# schem.net
KiCad netlist of a schematic drawn in EAGLE
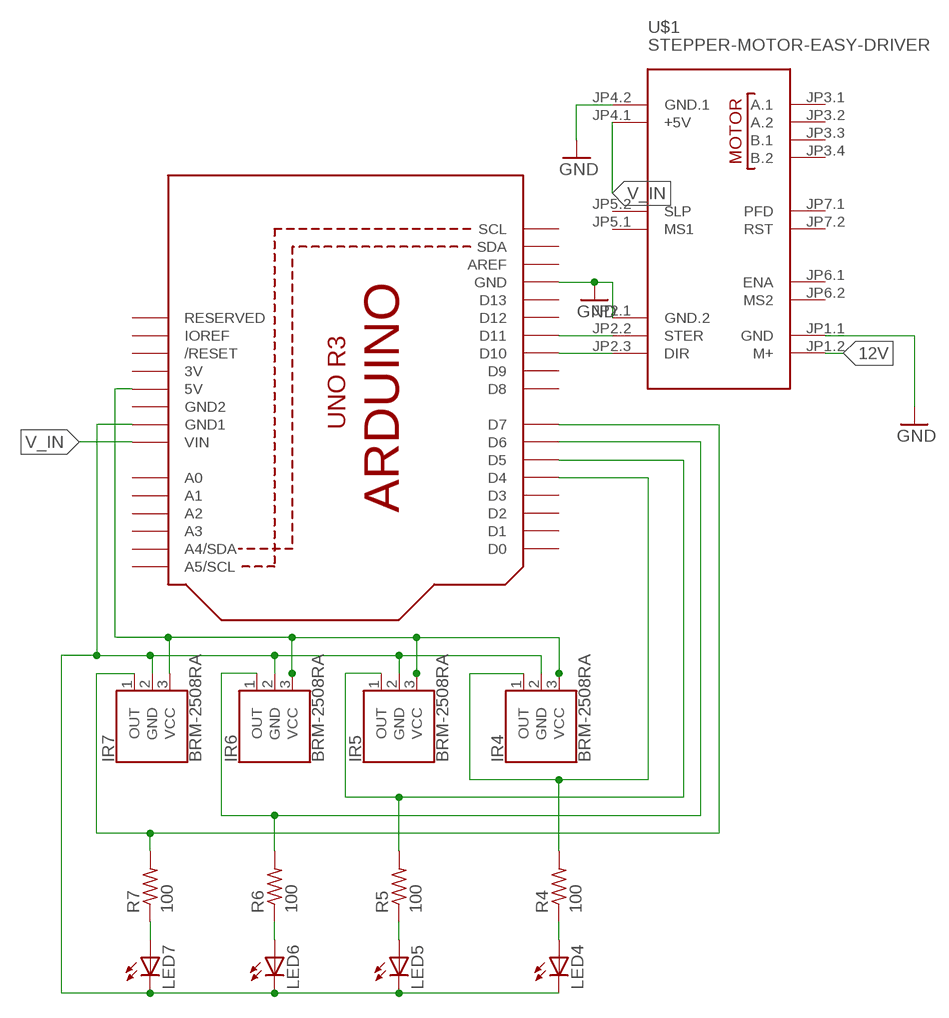
[diagram p0: schematic, sheet 1]

(export (version "E")
  (design (tool "Eeschema 10.0.6"))
  (components
    (comp (ref "IR4")
      (value "BRM-2508RA")
      (footprint "eagle-import:BRM-2508")
      (libsource (lib "eagle-import") (part "BRM-2508RA"))
    )
    (comp (ref "IR5")
      (value "BRM-2508RA")
      (footprint "eagle-import:BRM-2508")
      (libsource (lib "eagle-import") (part "BRM-2508RA"))
    )
    (comp (ref "IR6")
      (value "BRM-2508RA")
      (footprint "eagle-import:BRM-2508")
      (libsource (lib "eagle-import") (part "BRM-2508RA"))
    )
    (comp (ref "IR7")
      (value "BRM-2508RA")
      (footprint "eagle-import:BRM-2508")
      (libsource (lib "eagle-import") (part "BRM-2508RA"))
    )
    (comp (ref "LED4")
      (value "LED5MM")
      (footprint "eagle-import:LED5MM")
      (libsource (lib "eagle-import") (part "LED5MM"))
    )
    (comp (ref "LED5")
      (value "LED5MM")
      (footprint "eagle-import:LED5MM")
      (libsource (lib "eagle-import") (part "LED5MM"))
    )
    (comp (ref "LED6")
      (value "LED5MM")
      (footprint "eagle-import:LED5MM")
      (libsource (lib "eagle-import") (part "LED5MM"))
    )
    (comp (ref "LED7")
      (value "LED5MM")
      (footprint "eagle-import:LED5MM")
      (libsource (lib "eagle-import") (part "LED5MM"))
    )
    (comp (ref "R4")
      (value "100")
      (footprint "eagle-import:0805-THM")
      (libsource (lib "eagle-import") (part "FLIPFLOP-RES"))
    )
    (comp (ref "R5")
      (value "100")
      (footprint "eagle-import:0805-THM")
      (libsource (lib "eagle-import") (part "FLIPFLOP-RES"))
    )
    (comp (ref "R6")
      (value "100")
      (footprint "eagle-import:0805-THM")
      (libsource (lib "eagle-import") (part "FLIPFLOP-RES"))
    )
    (comp (ref "R7")
      (value "100")
      (footprint "eagle-import:0805-THM")
      (libsource (lib "eagle-import") (part "FLIPFLOP-RES"))
    )
    (comp (ref "U$1")
      (value "STEPPER-MOTOR-EASY-DRIVER")
      (footprint "eagle-import:STEPPER-MOTOR-EASY-DRIVER")
      (libsource (lib "eagle-import") (part "STEPPER-MOTOR-EASY-DRIVER"))
    )
    (comp (ref "U1")
      (value "ARDUINOR3-BPLACE")
      (footprint "eagle-import:ARDUINOR3-BPLACE")
      (libsource (lib "eagle-import") (part "ARDUINOR3-BPLACE"))
    )
  )
  (nets
    (net (code "1") (name "/3V") (class "Default")
      (node (ref "U1") (pin "3V") (pinfunction "3V_3V") (pintype "power_in"))
    )
    (net (code "2") (name "/GND2") (class "Default")
      (node (ref "U1") (pin "GND2") (pinfunction "GND2_GND2") (pintype "power_in"))
    )
    (net (code "3") (name "12V") (class "Default")
      (node (ref "U$1") (pin "JP1.2") (pinfunction "M+_JP1.2") (pintype "bidirectional"))
    )
    (net (code "4") (name "GND") (class "Default")
      (node (ref "U$1") (pin "JP1.1") (pinfunction "GND_JP1.1") (pintype "bidirectional"))
      (node (ref "U$1") (pin "JP2.1") (pinfunction "GND.2_JP2.1") (pintype "bidirectional"))
      (node (ref "U$1") (pin "JP4.2") (pinfunction "GND.1_JP4.2") (pintype "bidirectional"))
      (node (ref "U1") (pin "GND") (pinfunction "GND_GND") (pintype "power_in"))
    )
    (net (code "5") (name "Net-(IR4-GND)") (class "Default")
      (node (ref "IR4") (pin "2") (pinfunction "GND_2") (pintype "bidirectional"))
      (node (ref "IR5") (pin "2") (pinfunction "GND_2") (pintype "bidirectional"))
      (node (ref "IR6") (pin "2") (pinfunction "GND_2") (pintype "bidirectional"))
      (node (ref "IR7") (pin "2") (pinfunction "GND_2") (pintype "bidirectional"))
      (node (ref "LED4") (pin "K") (pinfunction "C_K") (pintype "passive"))
      (node (ref "LED5") (pin "K") (pinfunction "C_K") (pintype "passive"))
      (node (ref "LED6") (pin "K") (pinfunction "C_K") (pintype "passive"))
      (node (ref "LED7") (pin "K") (pinfunction "C_K") (pintype "passive"))
      (node (ref "U1") (pin "GND1") (pinfunction "GND1_GND1") (pintype "power_in"))
    )
    (net (code "6") (name "Net-(IR4-OUT)") (class "Default")
      (node (ref "IR4") (pin "1") (pinfunction "OUT_1") (pintype "bidirectional"))
      (node (ref "R4") (pin "2") (pinfunction "2_2") (pintype "passive"))
      (node (ref "U1") (pin "D4") (pinfunction "D4_D4") (pintype "bidirectional"))
    )
    (net (code "7") (name "Net-(IR4-VCC)") (class "Default")
      (node (ref "IR4") (pin "3") (pinfunction "VCC_3") (pintype "bidirectional"))
      (node (ref "IR5") (pin "3") (pinfunction "VCC_3") (pintype "bidirectional"))
      (node (ref "IR6") (pin "3") (pinfunction "VCC_3") (pintype "bidirectional"))
      (node (ref "IR7") (pin "3") (pinfunction "VCC_3") (pintype "bidirectional"))
      (node (ref "U1") (pin "5V") (pinfunction "5V_5V") (pintype "power_in"))
    )
    (net (code "8") (name "Net-(IR5-OUT)") (class "Default")
      (node (ref "IR5") (pin "1") (pinfunction "OUT_1") (pintype "bidirectional"))
      (node (ref "R5") (pin "2") (pinfunction "2_2") (pintype "passive"))
      (node (ref "U1") (pin "D5") (pinfunction "D5_D5") (pintype "bidirectional"))
    )
    (net (code "9") (name "Net-(IR6-OUT)") (class "Default")
      (node (ref "IR6") (pin "1") (pinfunction "OUT_1") (pintype "bidirectional"))
      (node (ref "R6") (pin "2") (pinfunction "2_2") (pintype "passive"))
      (node (ref "U1") (pin "D6") (pinfunction "D6_D6") (pintype "bidirectional"))
    )
    (net (code "10") (name "Net-(IR7-OUT)") (class "Default")
      (node (ref "IR7") (pin "1") (pinfunction "OUT_1") (pintype "bidirectional"))
      (node (ref "R7") (pin "2") (pinfunction "2_2") (pintype "passive"))
      (node (ref "U1") (pin "D7") (pinfunction "D7_D7") (pintype "bidirectional"))
    )
    (net (code "11") (name "Net-(LED4-PadA)") (class "Default")
      (node (ref "LED4") (pin "A") (pinfunction "A_A") (pintype "passive"))
      (node (ref "R4") (pin "1") (pinfunction "1_1") (pintype "passive"))
    )
    (net (code "12") (name "Net-(LED5-PadA)") (class "Default")
      (node (ref "LED5") (pin "A") (pinfunction "A_A") (pintype "passive"))
      (node (ref "R5") (pin "1") (pinfunction "1_1") (pintype "passive"))
    )
    (net (code "13") (name "Net-(LED6-PadA)") (class "Default")
      (node (ref "LED6") (pin "A") (pinfunction "A_A") (pintype "passive"))
      (node (ref "R6") (pin "1") (pinfunction "1_1") (pintype "passive"))
    )
    (net (code "14") (name "Net-(LED7-PadA)") (class "Default")
      (node (ref "LED7") (pin "A") (pinfunction "A_A") (pintype "passive"))
      (node (ref "R7") (pin "1") (pinfunction "1_1") (pintype "passive"))
    )
    (net (code "15") (name "Net-(U$1-DIR)") (class "Default")
      (node (ref "U$1") (pin "JP2.3") (pinfunction "DIR_JP2.3") (pintype "bidirectional"))
      (node (ref "U1") (pin "D10") (pinfunction "D10_D10") (pintype "bidirectional"))
    )
    (net (code "16") (name "Net-(U$1-STER)") (class "Default")
      (node (ref "U$1") (pin "JP2.2") (pinfunction "STER_JP2.2") (pintype "bidirectional"))
      (node (ref "U1") (pin "D11") (pinfunction "D11_D11") (pintype "bidirectional"))
    )
    (net (code "17") (name "V_IN") (class "Default")
      (node (ref "U$1") (pin "JP4.1") (pinfunction "+5V_JP4.1") (pintype "bidirectional"))
      (node (ref "U1") (pin "VIN") (pinfunction "VIN_VIN") (pintype "power_in"))
    )
    (net (code "18") (name "unconnected-(U$1-A.1-PadJP3.1)") (class "Default")
      (node (ref "U$1") (pin "JP3.1") (pinfunction "A.1_JP3.1") (pintype "bidirectional"))
    )
    (net (code "19") (name "unconnected-(U$1-A.2-PadJP3.2)") (class "Default")
      (node (ref "U$1") (pin "JP3.2") (pinfunction "A.2_JP3.2") (pintype "bidirectional"))
    )
    (net (code "20") (name "unconnected-(U$1-B.1-PadJP3.3)") (class "Default")
      (node (ref "U$1") (pin "JP3.3") (pinfunction "B.1_JP3.3") (pintype "bidirectional"))
    )
    (net (code "21") (name "unconnected-(U$1-B.2-PadJP3.4)") (class "Default")
      (node (ref "U$1") (pin "JP3.4") (pinfunction "B.2_JP3.4") (pintype "bidirectional"))
    )
    (net (code "22") (name "unconnected-(U$1-ENA-PadJP6.1)") (class "Default")
      (node (ref "U$1") (pin "JP6.1") (pinfunction "ENA_JP6.1") (pintype "bidirectional"))
    )
    (net (code "23") (name "unconnected-(U$1-MS1-PadJP5.1)") (class "Default")
      (node (ref "U$1") (pin "JP5.1") (pinfunction "MS1_JP5.1") (pintype "bidirectional"))
    )
    (net (code "24") (name "unconnected-(U$1-MS2-PadJP6.2)") (class "Default")
      (node (ref "U$1") (pin "JP6.2") (pinfunction "MS2_JP6.2") (pintype "bidirectional"))
    )
    (net (code "25") (name "unconnected-(U$1-PFD-PadJP7.1)") (class "Default")
      (node (ref "U$1") (pin "JP7.1") (pinfunction "PFD_JP7.1") (pintype "bidirectional"))
    )
    (net (code "26") (name "unconnected-(U$1-RST-PadJP7.2)") (class "Default")
      (node (ref "U$1") (pin "JP7.2") (pinfunction "RST_JP7.2") (pintype "bidirectional"))
    )
    (net (code "27") (name "unconnected-(U$1-SLP-PadJP5.2)") (class "Default")
      (node (ref "U$1") (pin "JP5.2") (pinfunction "SLP_JP5.2") (pintype "bidirectional"))
    )
    (net (code "28") (name "unconnected-(U1-A4{slash}SDA-PadA4)") (class "Default")
      (node (ref "U1") (pin "A4") (pinfunction "A4/SDA_A4") (pintype "bidirectional"))
    )
    (net (code "29") (name "unconnected-(U1-A5{slash}SCL-PadA5)") (class "Default")
      (node (ref "U1") (pin "A5") (pinfunction "A5/SCL_A5") (pintype "bidirectional"))
    )
    (net (code "30") (name "unconnected-(U1-PadA0)") (class "Default")
      (node (ref "U1") (pin "A0") (pinfunction "A0_A0") (pintype "bidirectional"))
    )
    (net (code "31") (name "unconnected-(U1-PadA1)") (class "Default")
      (node (ref "U1") (pin "A1") (pinfunction "A1_A1") (pintype "bidirectional"))
    )
    (net (code "32") (name "unconnected-(U1-PadA2)") (class "Default")
      (node (ref "U1") (pin "A2") (pinfunction "A2_A2") (pintype "bidirectional"))
    )
    (net (code "33") (name "unconnected-(U1-PadA3)") (class "Default")
      (node (ref "U1") (pin "A3") (pinfunction "A3_A3") (pintype "bidirectional"))
    )
    (net (code "34") (name "unconnected-(U1-PadAREF)") (class "Default")
      (node (ref "U1") (pin "AREF") (pinfunction "AREF_AREF") (pintype "bidirectional"))
    )
    (net (code "35") (name "unconnected-(U1-PadD0)") (class "Default")
      (node (ref "U1") (pin "D0") (pinfunction "D0_D0") (pintype "bidirectional"))
    )
    (net (code "36") (name "unconnected-(U1-PadD1)") (class "Default")
      (node (ref "U1") (pin "D1") (pinfunction "D1_D1") (pintype "bidirectional"))
    )
    (net (code "37") (name "unconnected-(U1-PadD2)") (class "Default")
      (node (ref "U1") (pin "D2") (pinfunction "D2_D2") (pintype "bidirectional"))
    )
    (net (code "38") (name "unconnected-(U1-PadD3)") (class "Default")
      (node (ref "U1") (pin "D3") (pinfunction "D3_D3") (pintype "bidirectional"))
    )
    (net (code "39") (name "unconnected-(U1-PadD8)") (class "Default")
      (node (ref "U1") (pin "D8") (pinfunction "D8_D8") (pintype "bidirectional"))
    )
    (net (code "40") (name "unconnected-(U1-PadD9)") (class "Default")
      (node (ref "U1") (pin "D9") (pinfunction "D9_D9") (pintype "bidirectional"))
    )
    (net (code "41") (name "unconnected-(U1-PadD12)") (class "Default")
      (node (ref "U1") (pin "D12") (pinfunction "D12_D12") (pintype "bidirectional"))
    )
    (net (code "42") (name "unconnected-(U1-PadD13)") (class "Default")
      (node (ref "U1") (pin "D13") (pinfunction "D13_D13") (pintype "bidirectional"))
    )
    (net (code "43") (name "unconnected-(U1-PadIOREF)") (class "Default")
      (node (ref "U1") (pin "IOREF") (pinfunction "IOREF_IOREF") (pintype "output"))
    )
    (net (code "44") (name "unconnected-(U1-PadRESERVED)") (class "Default")
      (node (ref "U1") (pin "RESERVED") (pinfunction "RESERVED_RESERVED") (pintype "no_connect"))
    )
    (net (code "45") (name "unconnected-(U1-PadSCL)") (class "Default")
      (node (ref "U1") (pin "SCL") (pinfunction "SCL_SCL") (pintype "bidirectional"))
    )
    (net (code "46") (name "unconnected-(U1-PadSDA)") (class "Default")
      (node (ref "U1") (pin "SDA") (pinfunction "SDA_SDA") (pintype "bidirectional"))
    )
    (net (code "47") (name "unconnected-(U1-{slash}RESET-PadRESET)") (class "Default")
      (node (ref "U1") (pin "RESET") (pinfunction "/RESET_RESET") (pintype "bidirectional"))
    )
  )
)
